# MT6815.net
KiCad netlist of a schematic drawn in Altium Designer
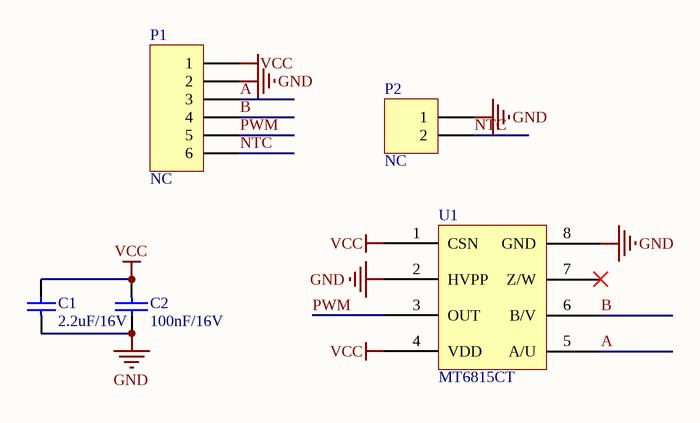
[diagram p0: MT6815.SchDoc]

(export (version "E")
  (design (tool "Eeschema 10.0.6"))
  (components
    (comp (ref "C1") (value "2.2uF/16V") (footprint "C0603") (libsource (lib "zijianku") (part "cap")))
    (comp (ref "C2")
      (value "100nF/16V")
      (footprint "C0402")
      (description "Capacitor")
      (libsource (lib "*") (part "CAP"))
    )
    (comp (ref "P1")
      (value "NC")
      (footprint "HDR1X6")
      (description "Header, 6-Pin")
      (fields (field (name "PUBLISHER") "Altium Limited"))
      (libsource (lib "Common Headers") (part "Header 6"))
    )
    (comp (ref "P2")
      (value "NC")
      (footprint "HDR1X2")
      (description "Header, 2-Pin")
      (fields (field (name "PUBLISHER") "Altium Limited"))
      (libsource (lib "Common Headers") (part "Header 2"))
    )
    (comp (ref "U1") (value "MT6815CT") (footprint "SOIC-8") (libsource (lib "zijianku") (part "MT6815CT")))
  )
  (nets
    (net (code "1") (name "/A") (class "Default")
      (node (ref "P1") (pin "3") (pinfunction "3_3") (pintype "passive"))
      (node (ref "U1") (pin "5") (pinfunction "A/U_5") (pintype "passive"))
    )
    (net (code "2") (name "/B") (class "Default")
      (node (ref "P1") (pin "4") (pinfunction "4_4") (pintype "passive"))
      (node (ref "U1") (pin "6") (pinfunction "B/V_6") (pintype "passive"))
    )
    (net (code "3") (name "/NTC") (class "Default")
      (node (ref "P1") (pin "6") (pinfunction "6_6") (pintype "passive"))
      (node (ref "P2") (pin "2") (pinfunction "2_2") (pintype "passive"))
    )
    (net (code "4") (name "/PWM") (class "Default")
      (node (ref "P1") (pin "5") (pinfunction "5_5") (pintype "passive"))
      (node (ref "U1") (pin "3") (pinfunction "OUT_3") (pintype "passive"))
    )
    (net (code "5") (name "GND") (class "Default")
      (node (ref "C1") (pin "1") (pinfunction "0_1") (pintype "passive"))
      (node (ref "C2") (pin "2") (pinfunction "2_2") (pintype "passive"))
      (node (ref "P1") (pin "2") (pinfunction "2_2") (pintype "passive"))
      (node (ref "P2") (pin "1") (pinfunction "1_1") (pintype "passive"))
      (node (ref "U1") (pin "2") (pinfunction "HVPP_2") (pintype "passive"))
      (node (ref "U1") (pin "8") (pinfunction "GND_8") (pintype "passive"))
    )
    (net (code "6") (name "VCC") (class "Default")
      (node (ref "C1") (pin "2") (pinfunction "1_2") (pintype "passive"))
      (node (ref "C2") (pin "1") (pinfunction "1_1") (pintype "passive"))
      (node (ref "P1") (pin "1") (pinfunction "1_1") (pintype "passive"))
      (node (ref "U1") (pin "1") (pinfunction "CSN_1") (pintype "passive"))
      (node (ref "U1") (pin "4") (pinfunction "VDD_4") (pintype "passive"))
    )
    (net (code "7") (name "unconnected-(U1-Z{slash}W-Pad7)") (class "Default")
      (node (ref "U1") (pin "7") (pinfunction "Z/W_7") (pintype "passive+no_connect"))
    )
  )
)
